# 2output.net
KiCad netlist of a schematic drawn in EAGLE
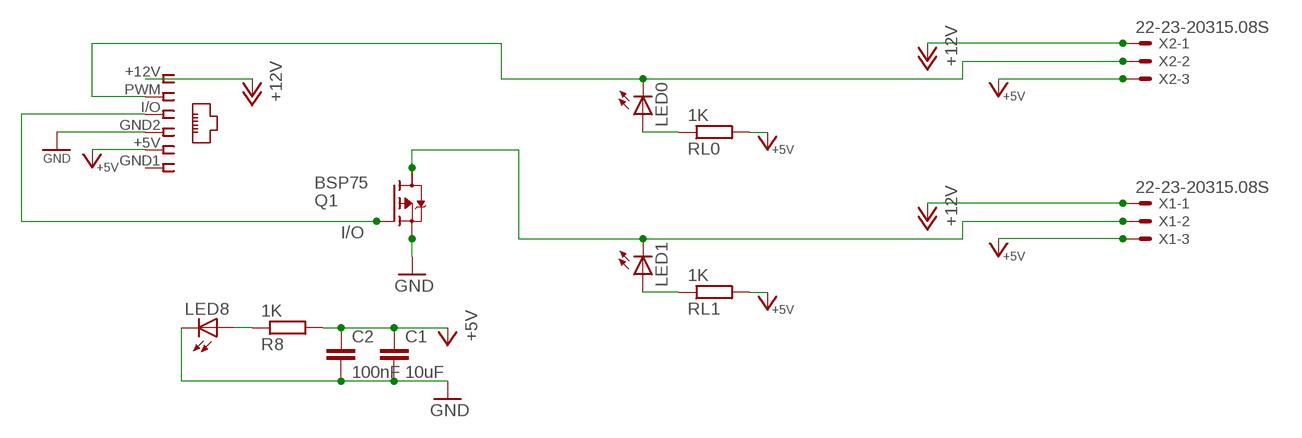
[diagram p0: schematic, sheet 1]

(export (version "E")
  (design (tool "Eeschema 10.0.6"))
  (components
    (comp (ref "C1")
      (value "10uF")
      (footprint "eagle-import:C1206")
      (libsource (lib "eagle-import") (part "C-EUC1206"))
    )
    (comp (ref "C2")
      (value "100nF")
      (footprint "eagle-import:C1206")
      (libsource (lib "eagle-import") (part "C-EUC1206"))
    )
    (comp (ref "I/O_PWM")
      (value "I2C 1")
      (footprint "eagle-import:RJ12-STRAIGHT")
      (libsource (lib "eagle-import") (part "RJ12STRAIGHT"))
    )
    (comp (ref "LED0")
      (value "LED1206")
      (footprint "eagle-import:LED-1206")
      (libsource (lib "eagle-import") (part "LED1206"))
    )
    (comp (ref "LED1")
      (value "LED1206")
      (footprint "eagle-import:LED-1206")
      (libsource (lib "eagle-import") (part "LED1206"))
    )
    (comp (ref "LED8")
      (value "LED1206")
      (footprint "eagle-import:LED-1206")
      (libsource (lib "eagle-import") (part "LED1206"))
    )
    (comp (ref "Q1")
      (value "BSP75")
      (footprint "eagle-import:PG-SOT-223")
      (libsource (lib "eagle-import") (part "BSP613P"))
    )
    (comp (ref "R8")
      (value "1K")
      (footprint "eagle-import:M1206")
      (libsource (lib "eagle-import") (part "R-EU_M1206"))
    )
    (comp (ref "RL0")
      (value "1K")
      (footprint "eagle-import:M1206")
      (libsource (lib "eagle-import") (part "R-EU_M1206"))
    )
    (comp (ref "RL1")
      (value "1K")
      (footprint "eagle-import:M1206")
      (libsource (lib "eagle-import") (part "R-EU_M1206"))
    )
    (comp (ref "X1")
      (value "22-23-20315.08S")
      (footprint "eagle-import:3-PIN-5.08S")
      (libsource (lib "eagle-import") (part "22-23-20315.08S"))
    )
    (comp (ref "X2")
      (value "22-23-20315.08S")
      (footprint "eagle-import:3-PIN-5.08S")
      (libsource (lib "eagle-import") (part "22-23-20315.08S"))
    )
  )
  (nets
    (net (code "1") (name "+5V") (class "Default")
      (node (ref "C1") (pin "1") (pinfunction "1_1") (pintype "passive"))
      (node (ref "C2") (pin "1") (pinfunction "1_1") (pintype "passive"))
      (node (ref "I/O_PWM") (pin "+5V") (pinfunction "5_+5V") (pintype "bidirectional"))
      (node (ref "R8") (pin "2") (pinfunction "2_2") (pintype "passive"))
      (node (ref "RL0") (pin "2") (pinfunction "2_2") (pintype "passive"))
      (node (ref "RL1") (pin "2") (pinfunction "2_2") (pintype "passive"))
      (node (ref "X1") (pin "3") (pinfunction "S_3") (pintype "passive"))
      (node (ref "X2") (pin "3") (pinfunction "S_3") (pintype "passive"))
    )
    (net (code "2") (name "+12V") (class "Default")
      (node (ref "I/O_PWM") (pin "+12V") (pinfunction "1_+12V") (pintype "bidirectional"))
      (node (ref "X1") (pin "1") (pinfunction "S_1") (pintype "passive"))
      (node (ref "X2") (pin "1") (pinfunction "S_1") (pintype "passive"))
    )
    (net (code "3") (name "/I{slash}O") (class "Default")
      (node (ref "I/O_PWM") (pin "I/O") (pinfunction "3_I/O") (pintype "bidirectional"))
      (node (ref "Q1") (pin "1") (pinfunction "G_1") (pintype "passive"))
    )
    (net (code "4") (name "GND") (class "Default")
      (node (ref "C1") (pin "2") (pinfunction "2_2") (pintype "passive"))
      (node (ref "C2") (pin "2") (pinfunction "2_2") (pintype "passive"))
      (node (ref "I/O_PWM") (pin "GND2") (pinfunction "4_GND2") (pintype "bidirectional"))
      (node (ref "LED8") (pin "C") (pinfunction "C_C") (pintype "passive"))
      (node (ref "Q1") (pin "3") (pinfunction "S_3") (pintype "passive"))
    )
    (net (code "5") (name "Net-(I/O_PWM-2)") (class "Default")
      (node (ref "I/O_PWM") (pin "PWM") (pinfunction "2_PWM") (pintype "bidirectional"))
      (node (ref "LED0") (pin "C") (pinfunction "C_C") (pintype "passive"))
      (node (ref "X2") (pin "2") (pinfunction "S_2") (pintype "passive"))
    )
    (net (code "6") (name "Net-(LED0-PadA)") (class "Default")
      (node (ref "LED0") (pin "A") (pinfunction "A_A") (pintype "passive"))
      (node (ref "RL0") (pin "1") (pinfunction "1_1") (pintype "passive"))
    )
    (net (code "7") (name "Net-(LED1-PadA)") (class "Default")
      (node (ref "LED1") (pin "A") (pinfunction "A_A") (pintype "passive"))
      (node (ref "RL1") (pin "1") (pinfunction "1_1") (pintype "passive"))
    )
    (net (code "8") (name "Net-(LED8-PadA)") (class "Default")
      (node (ref "LED8") (pin "A") (pinfunction "A_A") (pintype "passive"))
      (node (ref "R8") (pin "1") (pinfunction "1_1") (pintype "passive"))
    )
    (net (code "9") (name "Net-(X1B-S)") (class "Default")
      (node (ref "LED1") (pin "C") (pinfunction "C_C") (pintype "passive"))
      (node (ref "Q1") (pin "2") (pinfunction "D_2") (pintype "passive"))
      (node (ref "X1") (pin "2") (pinfunction "S_2") (pintype "passive"))
    )
    (net (code "10") (name "unconnected-(I/O_PWM-6-PadGND1)") (class "Default")
      (node (ref "I/O_PWM") (pin "GND1") (pinfunction "6_GND1") (pintype "bidirectional"))
    )
    (net (code "11") (name "unconnected-(Q1-D-Pad4)") (class "Default")
      (node (ref "Q1") (pin "4") (pinfunction "D_4") (pintype "passive"))
    )
  )
)
